# 1-Schematic_CessnaCitationX_AP_Front.net
KiCad netlist of a schematic drawn in EasyEDA
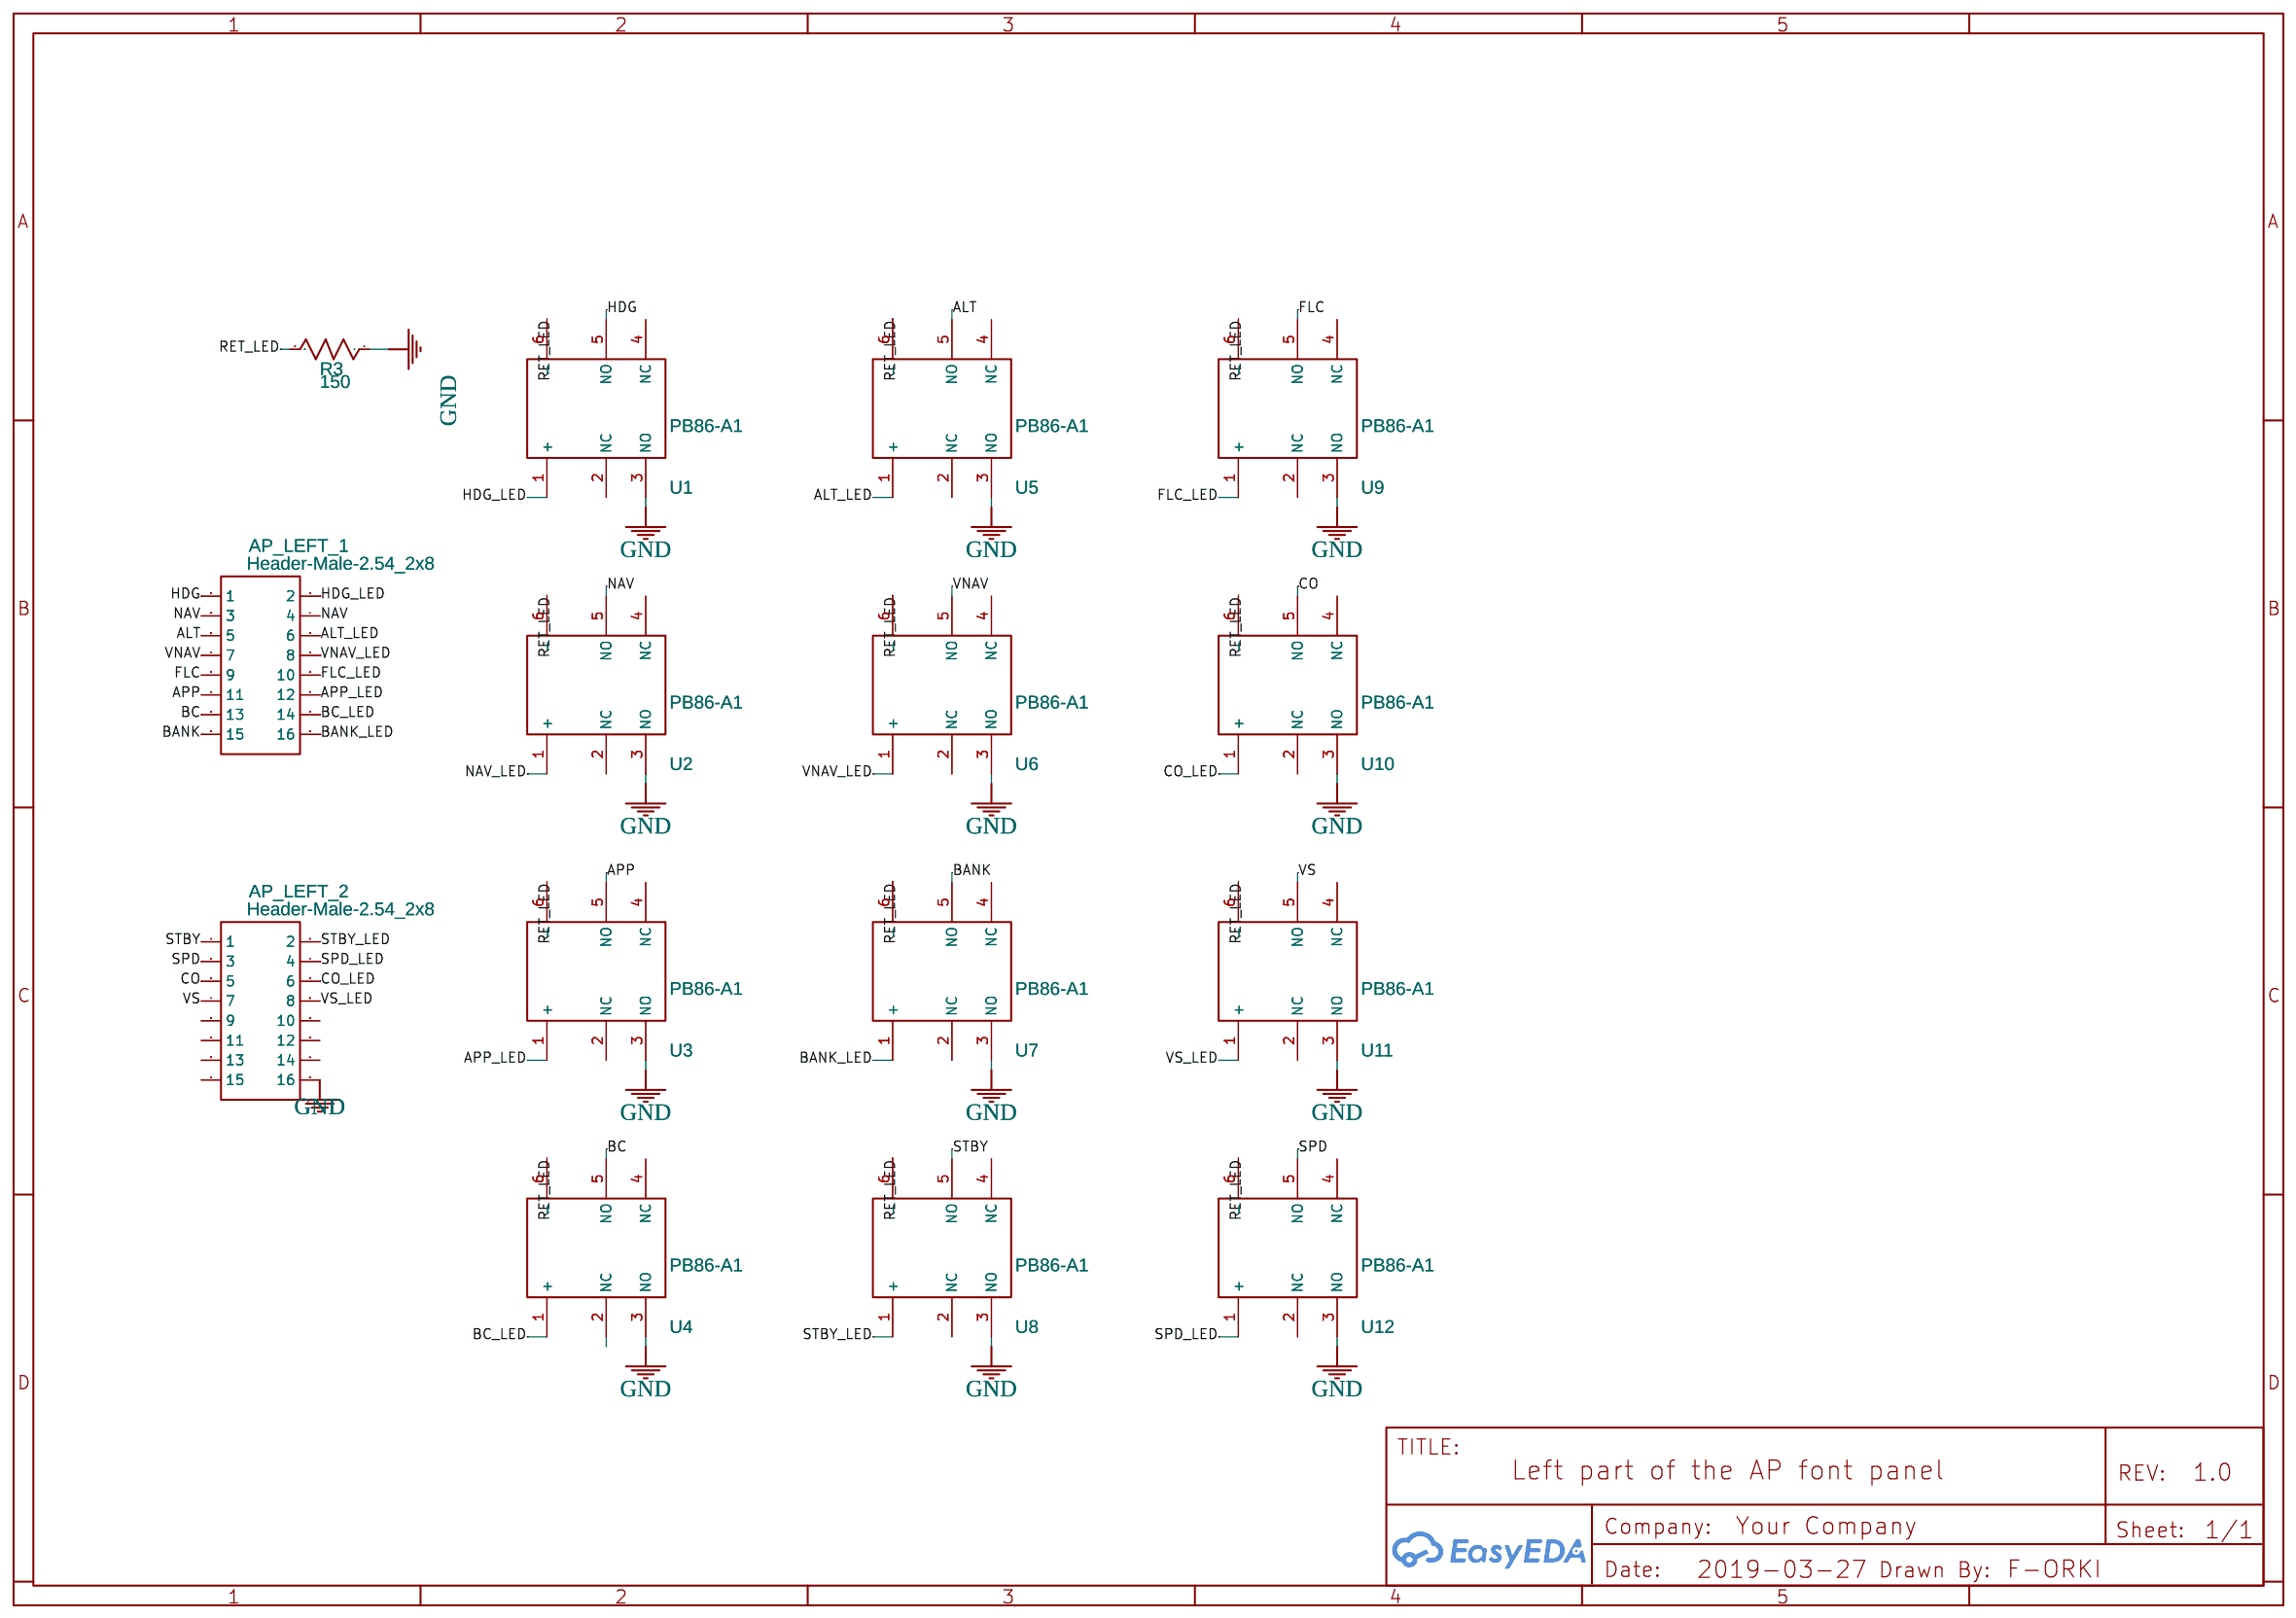
[diagram p0: PCB_AP_FRONT_LEFT]
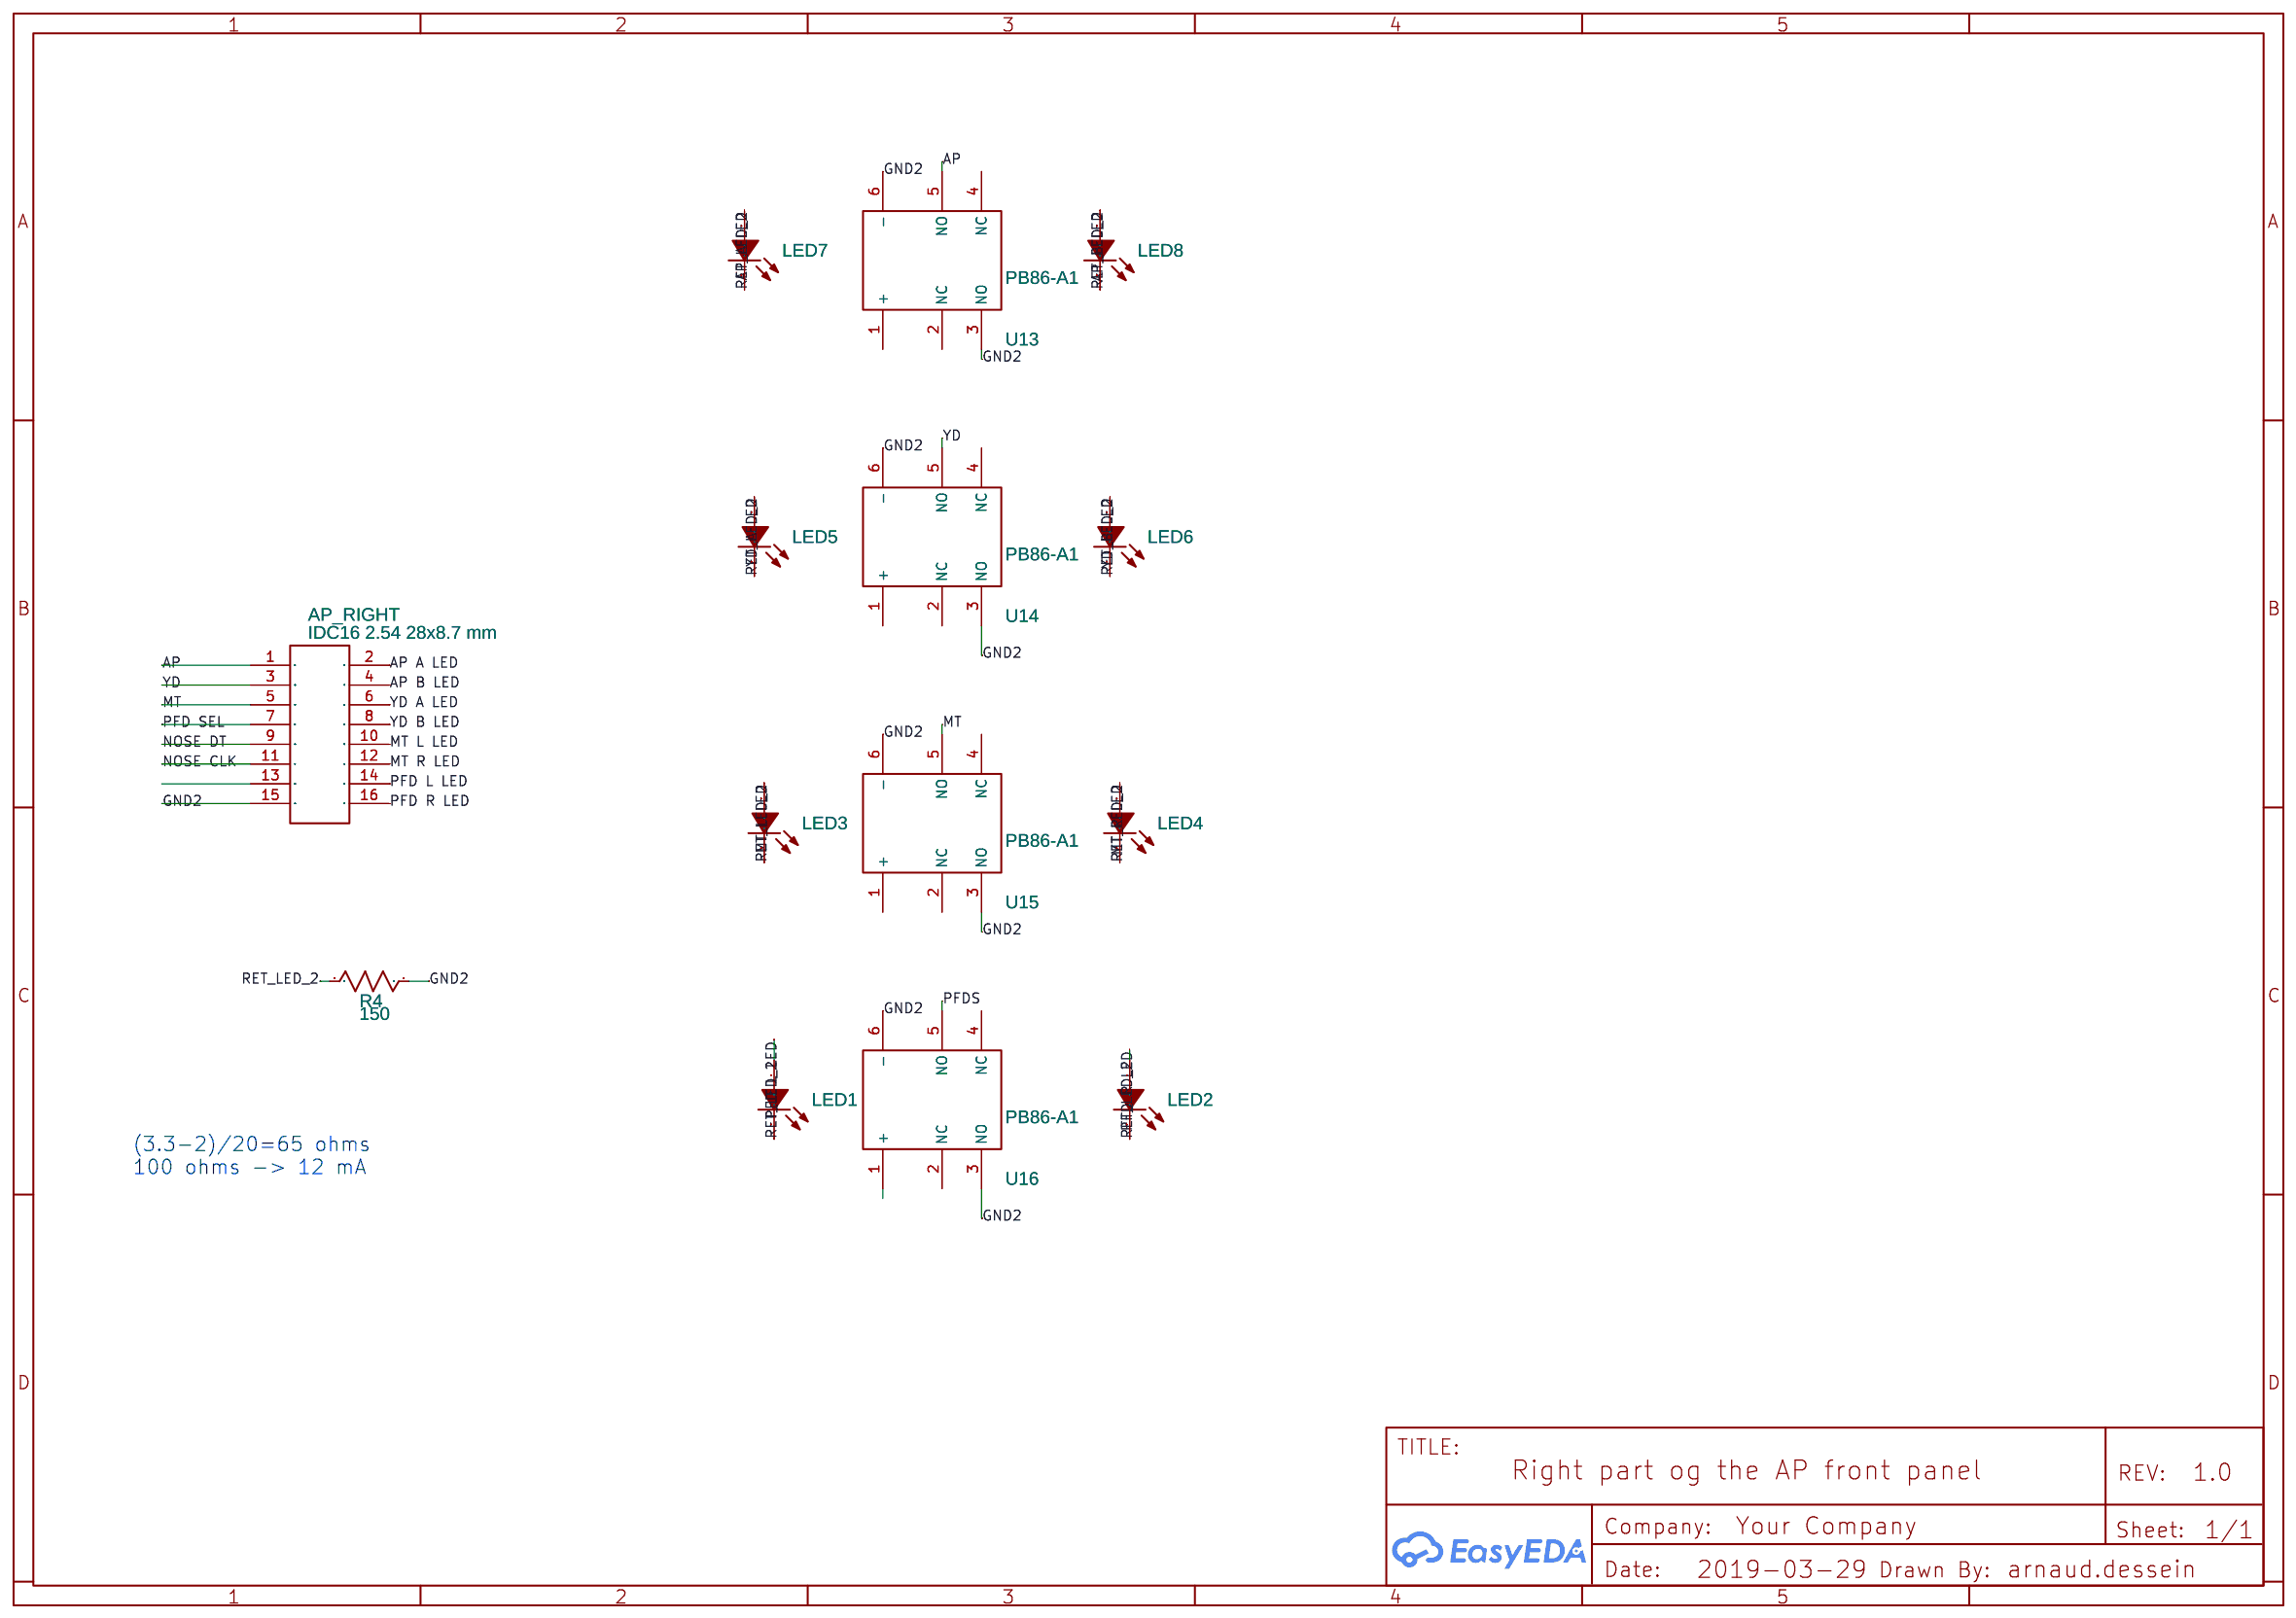
[diagram p1: PCB_AP_FRONT_RIGHT]

(export (version "E")
  (design (tool "Eeschema 10.0.6"))
  (components
    (comp (ref "AP_LEFT_1")
      (value "Header-Male-2.54_2x8")
      (fields
        (field (name "BOM_Manufacturer Part") "Double row straight 2*8Headers  Pins 2.54mm")
        (field (name "BOM_Supplier Part") "C68234")
      )
      (libsource (lib "") (part "Unknown_125_330"))
    )
    (comp (ref "AP_LEFT_2")
      (value "Header-Male-2.54_2x8")
      (fields
        (field (name "BOM_Manufacturer Part") "Double row straight 2*8Headers  Pins 2.54mm")
        (field (name "BOM_Supplier Part") "C68234")
      )
      (libsource (lib "") (part "Unknown_125_505"))
    )
    (comp (ref "R3")
      (value "150")
      (fields (field (name "BOM_Manufacturer Part") "?"))
      (libsource (lib "") (part "Res_AXIAL-0.3(1/8W)_US"))
    )
    (comp (ref "U1") (value "PB86-A1") (libsource (lib "") (part "Unknown_270_205")))
    (comp (ref "U2") (value "PB86-A1") (libsource (lib "") (part "Unknown_270_345")))
    (comp (ref "U3") (value "PB86-A1") (libsource (lib "") (part "Unknown_270_490")))
    (comp (ref "U4") (value "PB86-A1") (libsource (lib "") (part "Unknown_270_630")))
    (comp (ref "U5") (value "PB86-A1") (libsource (lib "") (part "Unknown_445_205")))
    (comp (ref "U6") (value "PB86-A1") (libsource (lib "") (part "Unknown_445_345")))
    (comp (ref "U7") (value "PB86-A1") (libsource (lib "") (part "Unknown_445_490")))
    (comp (ref "U8") (value "PB86-A1") (libsource (lib "") (part "Unknown_445_630")))
    (comp (ref "U9") (value "PB86-A1") (libsource (lib "") (part "Unknown_620_205")))
    (comp (ref "U10") (value "PB86-A1") (libsource (lib "") (part "Unknown_620_345")))
    (comp (ref "U11") (value "PB86-A1") (libsource (lib "") (part "Unknown_620_490")))
    (comp (ref "U12") (value "PB86-A1") (libsource (lib "") (part "Unknown_620_630")))
    (comp (ref "AP_RIGHT")
      (value "IDC16 2.54 28x8.7 mm")
      (fields (field (name "BOM_Manufacturer Part") "?"))
      (libsource (lib "") (part "Unknown_120_410"))
    )
    (comp (ref "LED1")
      (value "2A5Y3UD09 LED")
      (fields (field (name "BOM_Supplier Part") "C3651"))
      (libsource (lib "") (part "Unknown_390_550"))
    )
    (comp (ref "LED2")
      (value "2A5Y3UD09 LED")
      (fields (field (name "BOM_Supplier Part") "C3651"))
      (libsource (lib "") (part "Unknown_570_550"))
    )
    (comp (ref "LED3")
      (value "2A5Y3UD09 LED")
      (fields (field (name "BOM_Supplier Part") "C3651"))
      (libsource (lib "") (part "Unknown_385_410"))
    )
    (comp (ref "LED4")
      (value "2A5Y3UD09 LED")
      (fields (field (name "BOM_Supplier Part") "C3651"))
      (libsource (lib "") (part "Unknown_565_410"))
    )
    (comp (ref "LED5")
      (value "2A5Y3UD09 LED")
      (fields (field (name "BOM_Supplier Part") "C3651"))
      (libsource (lib "") (part "Unknown_380_265"))
    )
    (comp (ref "LED6")
      (value "2A5Y3UD09 LED")
      (fields (field (name "BOM_Supplier Part") "C3651"))
      (libsource (lib "") (part "Unknown_560_265"))
    )
    (comp (ref "LED7")
      (value "2A5Y3UD09 LED")
      (fields (field (name "BOM_Supplier Part") "C3651"))
      (libsource (lib "") (part "Unknown_375_120"))
    )
    (comp (ref "LED8")
      (value "2A5Y3UD09 LED")
      (fields (field (name "BOM_Supplier Part") "C3651"))
      (libsource (lib "") (part "Unknown_555_120"))
    )
    (comp (ref "R4")
      (value "150")
      (fields (field (name "BOM_Manufacturer Part") "?"))
      (libsource (lib "") (part "Res_AXIAL-0.3(1/8W)_US"))
    )
    (comp (ref "U13") (value "PB86-A1") (libsource (lib "") (part "Unknown_440_130")))
    (comp (ref "U14") (value "PB86-A1") (libsource (lib "") (part "Unknown_440_270")))
    (comp (ref "U15") (value "PB86-A1") (libsource (lib "") (part "Unknown_440_415")))
    (comp (ref "U16") (value "PB86-A1") (libsource (lib "") (part "Unknown_440_555")))
  )
  (nets
    (net (code "1") (name "ALT") (class "Default")
      (node (ref "AP_LEFT_1") (pin "5") (pinfunction "5_5") (pintype "input"))
      (node (ref "U5") (pin "5") (pinfunction "NO_5") (pintype "unspecified"))
    )
    (net (code "2") (name "ALT_LED") (class "Default")
      (node (ref "AP_LEFT_1") (pin "6") (pinfunction "6_6") (pintype "input"))
      (node (ref "U5") (pin "1") (pinfunction "+_1") (pintype "unspecified"))
    )
    (net (code "3") (name "AP") (class "Default")
      (node (ref "AP_RIGHT") (pin "1") (pinfunction "P1_1") (pintype "unspecified"))
      (node (ref "U13") (pin "5") (pinfunction "NO_5") (pintype "unspecified"))
    )
    (net (code "4") (name "AP A LED") (class "Default")
      (node (ref "AP_RIGHT") (pin "2") (pinfunction "P2_2") (pintype "unspecified"))
      (node (ref "LED7") (pin "1") (pinfunction "A_1") (pintype "unspecified"))
    )
    (net (code "5") (name "AP B LED") (class "Default")
      (node (ref "AP_RIGHT") (pin "4") (pinfunction "P4_4") (pintype "unspecified"))
      (node (ref "LED8") (pin "1") (pinfunction "A_1") (pintype "unspecified"))
    )
    (net (code "6") (name "APP") (class "Default")
      (node (ref "AP_LEFT_1") (pin "11") (pinfunction "11_11") (pintype "input"))
      (node (ref "U3") (pin "5") (pinfunction "NO_5") (pintype "unspecified"))
    )
    (net (code "7") (name "APP_LED") (class "Default")
      (node (ref "AP_LEFT_1") (pin "12") (pinfunction "12_12") (pintype "input"))
      (node (ref "U3") (pin "1") (pinfunction "+_1") (pintype "unspecified"))
    )
    (net (code "8") (name "BANK") (class "Default")
      (node (ref "AP_LEFT_1") (pin "15") (pinfunction "15_15") (pintype "input"))
      (node (ref "U7") (pin "5") (pinfunction "NO_5") (pintype "unspecified"))
    )
    (net (code "9") (name "BANK_LED") (class "Default")
      (node (ref "AP_LEFT_1") (pin "16") (pinfunction "16_16") (pintype "input"))
      (node (ref "U7") (pin "1") (pinfunction "+_1") (pintype "unspecified"))
    )
    (net (code "10") (name "BC") (class "Default")
      (node (ref "AP_LEFT_1") (pin "13") (pinfunction "13_13") (pintype "input"))
      (node (ref "U4") (pin "5") (pinfunction "NO_5") (pintype "unspecified"))
    )
    (net (code "11") (name "BC_LED") (class "Default")
      (node (ref "AP_LEFT_1") (pin "14") (pinfunction "14_14") (pintype "input"))
      (node (ref "U4") (pin "1") (pinfunction "+_1") (pintype "unspecified"))
    )
    (net (code "12") (name "CO") (class "Default")
      (node (ref "AP_LEFT_2") (pin "5") (pinfunction "5_5") (pintype "input"))
      (node (ref "U10") (pin "5") (pinfunction "NO_5") (pintype "unspecified"))
    )
    (net (code "13") (name "CO_LED") (class "Default")
      (node (ref "AP_LEFT_2") (pin "6") (pinfunction "6_6") (pintype "input"))
      (node (ref "U10") (pin "1") (pinfunction "+_1") (pintype "unspecified"))
    )
    (net (code "14") (name "FLC") (class "Default")
      (node (ref "AP_LEFT_1") (pin "9") (pinfunction "9_9") (pintype "input"))
      (node (ref "U9") (pin "5") (pinfunction "NO_5") (pintype "unspecified"))
    )
    (net (code "15") (name "FLC_LED") (class "Default")
      (node (ref "AP_LEFT_1") (pin "10") (pinfunction "10_10") (pintype "input"))
      (node (ref "U9") (pin "1") (pinfunction "+_1") (pintype "unspecified"))
    )
    (net (code "16") (name "GND") (class "Default")
      (node (ref "AP_LEFT_2") (pin "16") (pinfunction "16_16") (pintype "input"))
      (node (ref "R3") (pin "1") (pinfunction "1_1") (pintype "unspecified"))
      (node (ref "U1") (pin "3") (pinfunction "NO_3") (pintype "unspecified"))
      (node (ref "U10") (pin "3") (pinfunction "NO_3") (pintype "unspecified"))
      (node (ref "U11") (pin "3") (pinfunction "NO_3") (pintype "unspecified"))
      (node (ref "U12") (pin "3") (pinfunction "NO_3") (pintype "unspecified"))
      (node (ref "U2") (pin "3") (pinfunction "NO_3") (pintype "unspecified"))
      (node (ref "U3") (pin "3") (pinfunction "NO_3") (pintype "unspecified"))
      (node (ref "U4") (pin "3") (pinfunction "NO_3") (pintype "unspecified"))
      (node (ref "U5") (pin "3") (pinfunction "NO_3") (pintype "unspecified"))
      (node (ref "U6") (pin "3") (pinfunction "NO_3") (pintype "unspecified"))
      (node (ref "U7") (pin "3") (pinfunction "NO_3") (pintype "unspecified"))
      (node (ref "U8") (pin "3") (pinfunction "NO_3") (pintype "unspecified"))
      (node (ref "U9") (pin "3") (pinfunction "NO_3") (pintype "unspecified"))
    )
    (net (code "17") (name "GND2") (class "Default")
      (node (ref "AP_RIGHT") (pin "15") (pinfunction "15_15") (pintype "unspecified"))
      (node (ref "R4") (pin "1") (pinfunction "1_1") (pintype "unspecified"))
      (node (ref "U13") (pin "3") (pinfunction "NO_3") (pintype "unspecified"))
      (node (ref "U13") (pin "6") (pinfunction "-_6") (pintype "unspecified"))
      (node (ref "U14") (pin "3") (pinfunction "NO_3") (pintype "unspecified"))
      (node (ref "U14") (pin "6") (pinfunction "-_6") (pintype "unspecified"))
      (node (ref "U15") (pin "3") (pinfunction "NO_3") (pintype "unspecified"))
      (node (ref "U15") (pin "6") (pinfunction "-_6") (pintype "unspecified"))
      (node (ref "U16") (pin "3") (pinfunction "NO_3") (pintype "unspecified"))
      (node (ref "U16") (pin "6") (pinfunction "-_6") (pintype "unspecified"))
    )
    (net (code "18") (name "HDG") (class "Default")
      (node (ref "AP_LEFT_1") (pin "1") (pinfunction "1_1") (pintype "input"))
      (node (ref "U1") (pin "5") (pinfunction "NO_5") (pintype "unspecified"))
    )
    (net (code "19") (name "HDG_LED") (class "Default")
      (node (ref "AP_LEFT_1") (pin "2") (pinfunction "2_2") (pintype "input"))
      (node (ref "U1") (pin "1") (pinfunction "+_1") (pintype "unspecified"))
    )
    (net (code "20") (name "MT") (class "Default")
      (node (ref "AP_RIGHT") (pin "5") (pinfunction "P5_5") (pintype "unspecified"))
      (node (ref "U15") (pin "5") (pinfunction "NO_5") (pintype "unspecified"))
    )
    (net (code "21") (name "MT L LED") (class "Default")
      (node (ref "AP_RIGHT") (pin "10") (pinfunction "P10_10") (pintype "unspecified"))
      (node (ref "LED3") (pin "1") (pinfunction "A_1") (pintype "unspecified"))
    )
    (net (code "22") (name "MT R LED") (class "Default")
      (node (ref "AP_RIGHT") (pin "12") (pinfunction "12_12") (pintype "unspecified"))
      (node (ref "LED4") (pin "1") (pinfunction "A_1") (pintype "unspecified"))
    )
    (net (code "23") (name "NAV") (class "Default")
      (node (ref "AP_LEFT_1") (pin "3") (pinfunction "3_3") (pintype "input"))
      (node (ref "AP_LEFT_1") (pin "4") (pinfunction "4_4") (pintype "input"))
      (node (ref "U2") (pin "5") (pinfunction "NO_5") (pintype "unspecified"))
    )
    (net (code "24") (name "NAV_LED") (class "Default")
      (node (ref "U2") (pin "1") (pinfunction "+_1") (pintype "unspecified"))
    )
    (net (code "25") (name "NOSE CLK") (class "Default")
      (node (ref "AP_RIGHT") (pin "11") (pinfunction "11_11") (pintype "unspecified"))
    )
    (net (code "26") (name "NOSE DT") (class "Default")
      (node (ref "AP_RIGHT") (pin "9") (pinfunction "P9_9") (pintype "unspecified"))
    )
    (net (code "27") (name "PFD L LED") (class "Default")
      (node (ref "AP_RIGHT") (pin "14") (pinfunction "14_14") (pintype "unspecified"))
      (node (ref "LED1") (pin "1") (pinfunction "A_1") (pintype "unspecified"))
    )
    (net (code "28") (name "PFD R LED") (class "Default")
      (node (ref "AP_RIGHT") (pin "16") (pinfunction "16_16") (pintype "unspecified"))
      (node (ref "LED2") (pin "1") (pinfunction "A_1") (pintype "unspecified"))
    )
    (net (code "29") (name "PFD SEL") (class "Default")
      (node (ref "AP_RIGHT") (pin "7") (pinfunction "P7_7") (pintype "unspecified"))
    )
    (net (code "30") (name "PFDS") (class "Default")
      (node (ref "U16") (pin "5") (pinfunction "NO_5") (pintype "unspecified"))
    )
    (net (code "31") (name "RET_LED") (class "Default")
      (node (ref "R3") (pin "2") (pinfunction "2_2") (pintype "unspecified"))
      (node (ref "U1") (pin "6") (pinfunction "-_6") (pintype "unspecified"))
      (node (ref "U10") (pin "6") (pinfunction "-_6") (pintype "unspecified"))
      (node (ref "U11") (pin "6") (pinfunction "-_6") (pintype "unspecified"))
      (node (ref "U12") (pin "6") (pinfunction "-_6") (pintype "unspecified"))
      (node (ref "U2") (pin "6") (pinfunction "-_6") (pintype "unspecified"))
      (node (ref "U3") (pin "6") (pinfunction "-_6") (pintype "unspecified"))
      (node (ref "U4") (pin "6") (pinfunction "-_6") (pintype "unspecified"))
      (node (ref "U5") (pin "6") (pinfunction "-_6") (pintype "unspecified"))
      (node (ref "U6") (pin "6") (pinfunction "-_6") (pintype "unspecified"))
      (node (ref "U7") (pin "6") (pinfunction "-_6") (pintype "unspecified"))
      (node (ref "U8") (pin "6") (pinfunction "-_6") (pintype "unspecified"))
      (node (ref "U9") (pin "6") (pinfunction "-_6") (pintype "unspecified"))
    )
    (net (code "32") (name "RET_LED_2") (class "Default")
      (node (ref "LED1") (pin "2") (pinfunction "K_2") (pintype "unspecified"))
      (node (ref "LED2") (pin "2") (pinfunction "K_2") (pintype "unspecified"))
      (node (ref "LED3") (pin "2") (pinfunction "K_2") (pintype "unspecified"))
      (node (ref "LED4") (pin "2") (pinfunction "K_2") (pintype "unspecified"))
      (node (ref "LED5") (pin "2") (pinfunction "K_2") (pintype "unspecified"))
      (node (ref "LED6") (pin "2") (pinfunction "K_2") (pintype "unspecified"))
      (node (ref "LED7") (pin "2") (pinfunction "K_2") (pintype "unspecified"))
      (node (ref "LED8") (pin "2") (pinfunction "K_2") (pintype "unspecified"))
      (node (ref "R4") (pin "2") (pinfunction "2_2") (pintype "unspecified"))
    )
    (net (code "33") (name "SPD") (class "Default")
      (node (ref "AP_LEFT_2") (pin "3") (pinfunction "3_3") (pintype "input"))
      (node (ref "U12") (pin "5") (pinfunction "NO_5") (pintype "unspecified"))
    )
    (net (code "34") (name "SPD_LED") (class "Default")
      (node (ref "AP_LEFT_2") (pin "4") (pinfunction "4_4") (pintype "input"))
      (node (ref "U12") (pin "1") (pinfunction "+_1") (pintype "unspecified"))
    )
    (net (code "35") (name "STBY") (class "Default")
      (node (ref "AP_LEFT_2") (pin "1") (pinfunction "1_1") (pintype "input"))
      (node (ref "U8") (pin "5") (pinfunction "NO_5") (pintype "unspecified"))
    )
    (net (code "36") (name "STBY_LED") (class "Default")
      (node (ref "AP_LEFT_2") (pin "2") (pinfunction "2_2") (pintype "input"))
      (node (ref "U8") (pin "1") (pinfunction "+_1") (pintype "unspecified"))
    )
    (net (code "37") (name "VNAV") (class "Default")
      (node (ref "AP_LEFT_1") (pin "7") (pinfunction "7_7") (pintype "input"))
      (node (ref "U6") (pin "5") (pinfunction "NO_5") (pintype "unspecified"))
    )
    (net (code "38") (name "VNAV_LED") (class "Default")
      (node (ref "AP_LEFT_1") (pin "8") (pinfunction "8_8") (pintype "input"))
      (node (ref "U6") (pin "1") (pinfunction "+_1") (pintype "unspecified"))
    )
    (net (code "39") (name "VS") (class "Default")
      (node (ref "AP_LEFT_2") (pin "7") (pinfunction "7_7") (pintype "input"))
      (node (ref "U11") (pin "5") (pinfunction "NO_5") (pintype "unspecified"))
    )
    (net (code "40") (name "VS_LED") (class "Default")
      (node (ref "AP_LEFT_2") (pin "8") (pinfunction "8_8") (pintype "input"))
      (node (ref "U11") (pin "1") (pinfunction "+_1") (pintype "unspecified"))
    )
    (net (code "41") (name "YD") (class "Default")
      (node (ref "AP_RIGHT") (pin "3") (pinfunction "P3_3") (pintype "unspecified"))
      (node (ref "U14") (pin "5") (pinfunction "NO_5") (pintype "unspecified"))
    )
    (net (code "42") (name "YD A LED") (class "Default")
      (node (ref "AP_RIGHT") (pin "6") (pinfunction "P6_6") (pintype "unspecified"))
      (node (ref "LED5") (pin "1") (pinfunction "A_1") (pintype "unspecified"))
    )
    (net (code "43") (name "YD B LED") (class "Default")
      (node (ref "AP_RIGHT") (pin "8") (pinfunction "P8_8") (pintype "unspecified"))
      (node (ref "LED6") (pin "1") (pinfunction "A_1") (pintype "unspecified"))
    )
    (net (code "44") (name "unconnected-(AP_LEFT_2-Pad9)") (class "Default")
      (node (ref "AP_LEFT_2") (pin "9") (pinfunction "9_9") (pintype "input"))
    )
    (net (code "45") (name "unconnected-(AP_LEFT_2-Pad10)") (class "Default")
      (node (ref "AP_LEFT_2") (pin "10") (pinfunction "10_10") (pintype "input"))
    )
    (net (code "46") (name "unconnected-(AP_LEFT_2-Pad11)") (class "Default")
      (node (ref "AP_LEFT_2") (pin "11") (pinfunction "11_11") (pintype "input"))
    )
    (net (code "47") (name "unconnected-(AP_LEFT_2-Pad12)") (class "Default")
      (node (ref "AP_LEFT_2") (pin "12") (pinfunction "12_12") (pintype "input"))
    )
    (net (code "48") (name "unconnected-(AP_LEFT_2-Pad13)") (class "Default")
      (node (ref "AP_LEFT_2") (pin "13") (pinfunction "13_13") (pintype "input"))
    )
    (net (code "49") (name "unconnected-(AP_LEFT_2-Pad14)") (class "Default")
      (node (ref "AP_LEFT_2") (pin "14") (pinfunction "14_14") (pintype "input"))
    )
    (net (code "50") (name "unconnected-(AP_LEFT_2-Pad15)") (class "Default")
      (node (ref "AP_LEFT_2") (pin "15") (pinfunction "15_15") (pintype "input"))
    )
    (net (code "51") (name "unconnected-(AP_RIGHT-Pad13)") (class "Default")
      (node (ref "AP_RIGHT") (pin "13") (pinfunction "13_13") (pintype "unspecified"))
    )
    (net (code "52") (name "unconnected-(U1-NC-Pad2)") (class "Default")
      (node (ref "U1") (pin "2") (pinfunction "NC_2") (pintype "unspecified"))
    )
    (net (code "53") (name "unconnected-(U1-NC-Pad4)") (class "Default")
      (node (ref "U1") (pin "4") (pinfunction "NC_4") (pintype "unspecified"))
    )
    (net (code "54") (name "unconnected-(U2-NC-Pad2)") (class "Default")
      (node (ref "U2") (pin "2") (pinfunction "NC_2") (pintype "unspecified"))
    )
    (net (code "55") (name "unconnected-(U2-NC-Pad4)") (class "Default")
      (node (ref "U2") (pin "4") (pinfunction "NC_4") (pintype "unspecified"))
    )
    (net (code "56") (name "unconnected-(U3-NC-Pad2)") (class "Default")
      (node (ref "U3") (pin "2") (pinfunction "NC_2") (pintype "unspecified"))
    )
    (net (code "57") (name "unconnected-(U3-NC-Pad4)") (class "Default")
      (node (ref "U3") (pin "4") (pinfunction "NC_4") (pintype "unspecified"))
    )
    (net (code "58") (name "unconnected-(U4-NC-Pad2)") (class "Default")
      (node (ref "U4") (pin "2") (pinfunction "NC_2") (pintype "unspecified"))
    )
    (net (code "59") (name "unconnected-(U4-NC-Pad4)") (class "Default")
      (node (ref "U4") (pin "4") (pinfunction "NC_4") (pintype "unspecified"))
    )
    (net (code "60") (name "unconnected-(U5-NC-Pad2)") (class "Default")
      (node (ref "U5") (pin "2") (pinfunction "NC_2") (pintype "unspecified"))
    )
    (net (code "61") (name "unconnected-(U5-NC-Pad4)") (class "Default")
      (node (ref "U5") (pin "4") (pinfunction "NC_4") (pintype "unspecified"))
    )
    (net (code "62") (name "unconnected-(U6-NC-Pad2)") (class "Default")
      (node (ref "U6") (pin "2") (pinfunction "NC_2") (pintype "unspecified"))
    )
    (net (code "63") (name "unconnected-(U6-NC-Pad4)") (class "Default")
      (node (ref "U6") (pin "4") (pinfunction "NC_4") (pintype "unspecified"))
    )
    (net (code "64") (name "unconnected-(U7-NC-Pad2)") (class "Default")
      (node (ref "U7") (pin "2") (pinfunction "NC_2") (pintype "unspecified"))
    )
    (net (code "65") (name "unconnected-(U7-NC-Pad4)") (class "Default")
      (node (ref "U7") (pin "4") (pinfunction "NC_4") (pintype "unspecified"))
    )
    (net (code "66") (name "unconnected-(U8-NC-Pad2)") (class "Default")
      (node (ref "U8") (pin "2") (pinfunction "NC_2") (pintype "unspecified"))
    )
    (net (code "67") (name "unconnected-(U8-NC-Pad4)") (class "Default")
      (node (ref "U8") (pin "4") (pinfunction "NC_4") (pintype "unspecified"))
    )
    (net (code "68") (name "unconnected-(U9-NC-Pad2)") (class "Default")
      (node (ref "U9") (pin "2") (pinfunction "NC_2") (pintype "unspecified"))
    )
    (net (code "69") (name "unconnected-(U9-NC-Pad4)") (class "Default")
      (node (ref "U9") (pin "4") (pinfunction "NC_4") (pintype "unspecified"))
    )
    (net (code "70") (name "unconnected-(U10-NC-Pad2)") (class "Default")
      (node (ref "U10") (pin "2") (pinfunction "NC_2") (pintype "unspecified"))
    )
    (net (code "71") (name "unconnected-(U10-NC-Pad4)") (class "Default")
      (node (ref "U10") (pin "4") (pinfunction "NC_4") (pintype "unspecified"))
    )
    (net (code "72") (name "unconnected-(U11-NC-Pad2)") (class "Default")
      (node (ref "U11") (pin "2") (pinfunction "NC_2") (pintype "unspecified"))
    )
    (net (code "73") (name "unconnected-(U11-NC-Pad4)") (class "Default")
      (node (ref "U11") (pin "4") (pinfunction "NC_4") (pintype "unspecified"))
    )
    (net (code "74") (name "unconnected-(U12-NC-Pad2)") (class "Default")
      (node (ref "U12") (pin "2") (pinfunction "NC_2") (pintype "unspecified"))
    )
    (net (code "75") (name "unconnected-(U12-NC-Pad4)") (class "Default")
      (node (ref "U12") (pin "4") (pinfunction "NC_4") (pintype "unspecified"))
    )
    (net (code "76") (name "unconnected-(U13-+-Pad1)") (class "Default")
      (node (ref "U13") (pin "1") (pinfunction "+_1") (pintype "unspecified"))
    )
    (net (code "77") (name "unconnected-(U13-NC-Pad2)") (class "Default")
      (node (ref "U13") (pin "2") (pinfunction "NC_2") (pintype "unspecified"))
    )
    (net (code "78") (name "unconnected-(U13-NC-Pad4)") (class "Default")
      (node (ref "U13") (pin "4") (pinfunction "NC_4") (pintype "unspecified"))
    )
    (net (code "79") (name "unconnected-(U14-+-Pad1)") (class "Default")
      (node (ref "U14") (pin "1") (pinfunction "+_1") (pintype "unspecified"))
    )
    (net (code "80") (name "unconnected-(U14-NC-Pad2)") (class "Default")
      (node (ref "U14") (pin "2") (pinfunction "NC_2") (pintype "unspecified"))
    )
    (net (code "81") (name "unconnected-(U14-NC-Pad4)") (class "Default")
      (node (ref "U14") (pin "4") (pinfunction "NC_4") (pintype "unspecified"))
    )
    (net (code "82") (name "unconnected-(U15-+-Pad1)") (class "Default")
      (node (ref "U15") (pin "1") (pinfunction "+_1") (pintype "unspecified"))
    )
    (net (code "83") (name "unconnected-(U15-NC-Pad2)") (class "Default")
      (node (ref "U15") (pin "2") (pinfunction "NC_2") (pintype "unspecified"))
    )
    (net (code "84") (name "unconnected-(U15-NC-Pad4)") (class "Default")
      (node (ref "U15") (pin "4") (pinfunction "NC_4") (pintype "unspecified"))
    )
    (net (code "85") (name "unconnected-(U16-+-Pad1)") (class "Default")
      (node (ref "U16") (pin "1") (pinfunction "+_1") (pintype "unspecified"))
    )
    (net (code "86") (name "unconnected-(U16-NC-Pad2)") (class "Default")
      (node (ref "U16") (pin "2") (pinfunction "NC_2") (pintype "unspecified"))
    )
    (net (code "87") (name "unconnected-(U16-NC-Pad4)") (class "Default")
      (node (ref "U16") (pin "4") (pinfunction "NC_4") (pintype "unspecified"))
    )
  )
)
